# SCHEMATIC.net
KiCad netlist of a schematic drawn in EAGLE
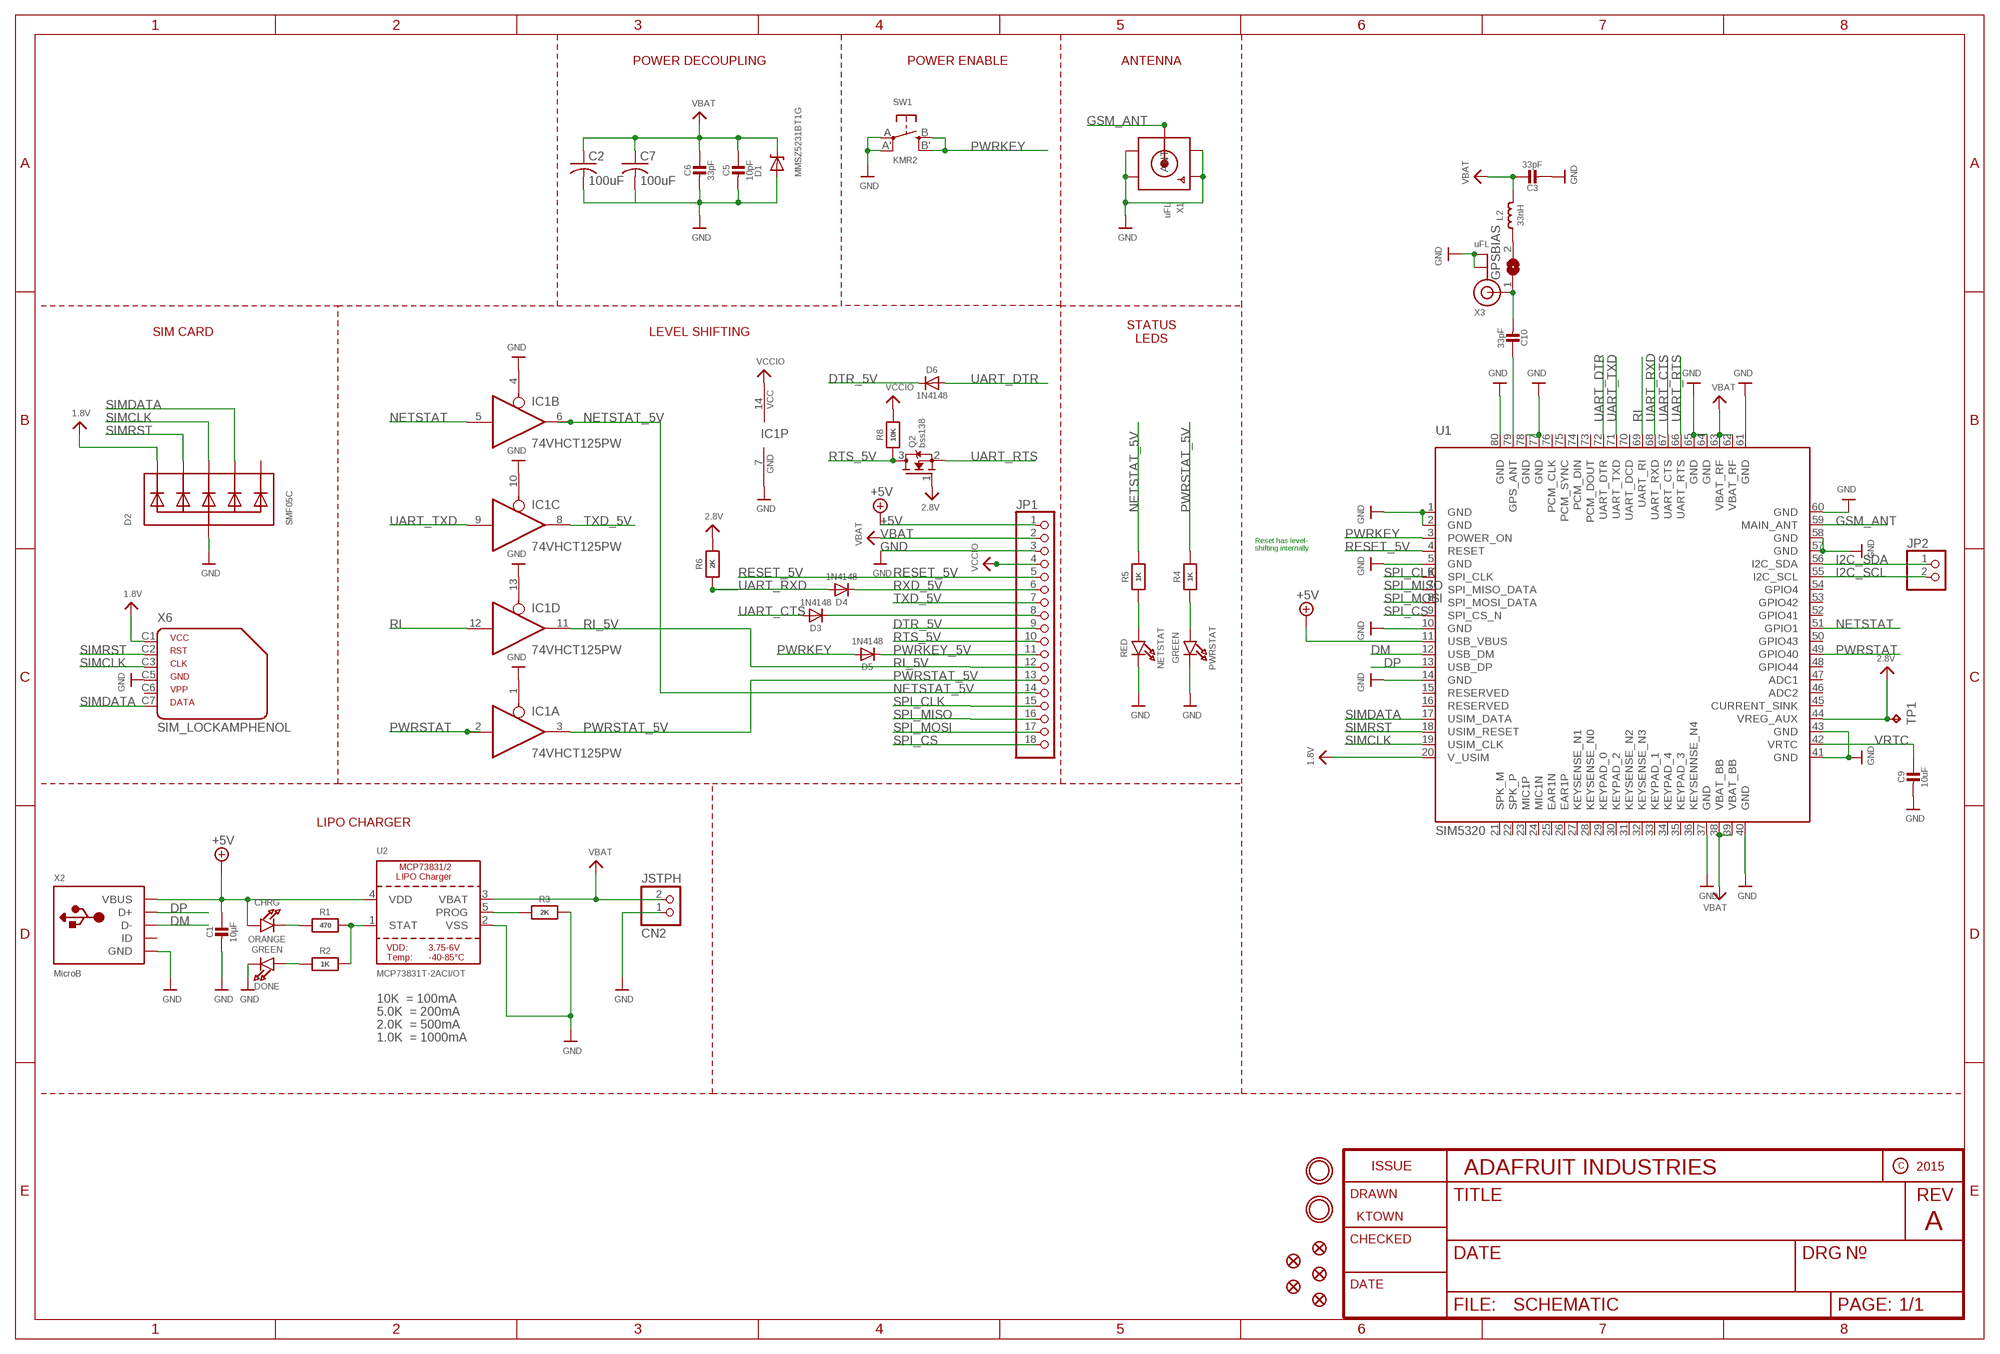
[diagram p0: schematic, sheet 1]

(export (version "E")
  (design (tool "Eeschema 10.0.6"))
  (components
    (comp (ref "C1")
      (value "10µF")
      (footprint "eagle-import:0805-NO")
      (libsource (lib "eagle-import") (part "CAP_CERAMIC0805-NOOUTLINE"))
    )
    (comp (ref "C2")
      (value "100uF")
      (footprint "eagle-import:C1210")
      (libsource (lib "eagle-import") (part "C-USC1210"))
    )
    (comp (ref "C3")
      (value "33pF")
      (footprint "eagle-import:0805-NO")
      (libsource (lib "eagle-import") (part "CAP_CERAMIC0805-NOOUTLINE"))
    )
    (comp (ref "C5")
      (value "10pF")
      (footprint "eagle-import:0805-NO")
      (libsource (lib "eagle-import") (part "CAP_CERAMIC0805-NOOUTLINE"))
    )
    (comp (ref "C6")
      (value "33pF")
      (footprint "eagle-import:0805-NO")
      (libsource (lib "eagle-import") (part "CAP_CERAMIC0805-NOOUTLINE"))
    )
    (comp (ref "C7")
      (value "100uF")
      (footprint "eagle-import:C1210")
      (libsource (lib "eagle-import") (part "C-USC1210"))
    )
    (comp (ref "C9")
      (value "10uF")
      (footprint "eagle-import:0805-NO")
      (libsource (lib "eagle-import") (part "CAP_CERAMIC0805-NOOUTLINE"))
    )
    (comp (ref "C10")
      (value "33pF")
      (footprint "eagle-import:0805-NO")
      (libsource (lib "eagle-import") (part "CAP_CERAMIC0805-NOOUTLINE"))
    )
    (comp (ref "CHRG")
      (value "ORANGE")
      (footprint "eagle-import:CHIPLED_0805_NOOUTLINE")
      (libsource (lib "eagle-import") (part "LED0805_NOOUTLINE"))
    )
    (comp (ref "CN2")
      (value "JSTPH")
      (footprint "eagle-import:JSTPH2")
      (libsource (lib "eagle-import") (part "JST_2PIN"))
    )
    (comp (ref "D1")
      (value "MMSZ5231BT1G")
      (footprint "eagle-import:SOD-123")
      (libsource (lib "eagle-import") (part "DIODE-ZENERSOD123"))
    )
    (comp (ref "D2")
      (value "SMF05C")
      (footprint "eagle-import:SOT363")
      (libsource (lib "eagle-import") (part "TVSARRAY_5LANE"))
    )
    (comp (ref "D3")
      (value "1N4148")
      (footprint "eagle-import:SOD-323")
      (libsource (lib "eagle-import") (part "DIODESOD-323"))
    )
    (comp (ref "D4")
      (value "1N4148")
      (footprint "eagle-import:SOD-323")
      (libsource (lib "eagle-import") (part "DIODESOD-323"))
    )
    (comp (ref "D5")
      (value "1N4148")
      (footprint "eagle-import:SOD-323")
      (libsource (lib "eagle-import") (part "DIODESOD-323"))
    )
    (comp (ref "D6")
      (value "1N4148")
      (footprint "eagle-import:SOD-323")
      (libsource (lib "eagle-import") (part "DIODESOD-323"))
    )
    (comp (ref "DONE")
      (value "GREEN")
      (footprint "eagle-import:CHIPLED_0805_NOOUTLINE")
      (libsource (lib "eagle-import") (part "LED0805_NOOUTLINE"))
    )
    (comp (ref "FID1")
      (value "FIDUCIAL\"\"")
      (footprint "eagle-import:FIDUCIAL_1MM")
      (libsource (lib "eagle-import") (part "FIDUCIAL{dblquote}{dblquote}"))
    )
    (comp (ref "FID2")
      (value "FIDUCIAL\"\"")
      (footprint "eagle-import:FIDUCIAL_1MM")
      (libsource (lib "eagle-import") (part "FIDUCIAL{dblquote}{dblquote}"))
    )
    (comp (ref "FID3")
      (value "FIDUCIAL\"\"")
      (footprint "eagle-import:FIDUCIAL_1MM")
      (libsource (lib "eagle-import") (part "FIDUCIAL{dblquote}{dblquote}"))
    )
    (comp (ref "FID4")
      (value "FIDUCIAL\"\"")
      (footprint "eagle-import:FIDUCIAL_1MM")
      (libsource (lib "eagle-import") (part "FIDUCIAL{dblquote}{dblquote}"))
    )
    (comp (ref "FID5")
      (value "FIDUCIAL\"\"")
      (footprint "eagle-import:FIDUCIAL_1MM")
      (libsource (lib "eagle-import") (part "FIDUCIAL{dblquote}{dblquote}"))
    )
    (comp (ref "GPSBIAS")
      (value "SOLDERJUMPER")
      (footprint "eagle-import:SOLDERJUMPER_ARROW_NOPASTE")
      (libsource (lib "eagle-import") (part "SOLDERJUMPER"))
    )
    (comp (ref "IC1")
      (value "74VHCT125PW")
      (footprint "eagle-import:TSSOP14")
      (libsource (lib "eagle-import") (part "74125PWABT"))
    )
    (comp (ref "JP1")
      (value "HEADER-1X18")
      (footprint "eagle-import:1X18_ROUND70")
      (libsource (lib "eagle-import") (part "HEADER-1X18"))
    )
    (comp (ref "JP2")
      (value "HEADER-1X2ROUND")
      (footprint "eagle-import:1X02_ROUND")
      (libsource (lib "eagle-import") (part "HEADER-1X2ROUND"))
    )
    (comp (ref "L2")
      (value "33nH")
      (footprint "eagle-import:_0805MP")
      (libsource (lib "eagle-import") (part "INDUCTOR_0805MP"))
    )
    (comp (ref "NETSTAT")
      (value "RED")
      (footprint "eagle-import:CHIPLED_0805_NOOUTLINE")
      (libsource (lib "eagle-import") (part "LED0805_NOOUTLINE"))
    )
    (comp (ref "PWRSTAT")
      (value "GREEN")
      (footprint "eagle-import:CHIPLED_0805_NOOUTLINE")
      (libsource (lib "eagle-import") (part "LED0805_NOOUTLINE"))
    )
    (comp (ref "Q2")
      (value "bss138")
      (footprint "eagle-import:SOT23-WIDE")
      (libsource (lib "eagle-import") (part "MOSFET-NWIDE"))
    )
    (comp (ref "R1")
      (value "470")
      (footprint "eagle-import:0805-NO")
      (libsource (lib "eagle-import") (part "RESISTOR0805_NOOUTLINE"))
    )
    (comp (ref "R2")
      (value "1K")
      (footprint "eagle-import:0805-NO")
      (libsource (lib "eagle-import") (part "RESISTOR0805_NOOUTLINE"))
    )
    (comp (ref "R3")
      (value "2K")
      (footprint "eagle-import:0805-NO")
      (libsource (lib "eagle-import") (part "RESISTOR0805_NOOUTLINE"))
    )
    (comp (ref "R4")
      (value "1K")
      (footprint "eagle-import:0805-NO")
      (libsource (lib "eagle-import") (part "RESISTOR0805_NOOUTLINE"))
    )
    (comp (ref "R5")
      (value "1K")
      (footprint "eagle-import:0805-NO")
      (libsource (lib "eagle-import") (part "RESISTOR0805_NOOUTLINE"))
    )
    (comp (ref "R6")
      (value "2K")
      (footprint "eagle-import:0805-NO")
      (libsource (lib "eagle-import") (part "RESISTOR0805_NOOUTLINE"))
    )
    (comp (ref "R8")
      (value "10K")
      (footprint "eagle-import:0805-NO")
      (libsource (lib "eagle-import") (part "RESISTOR0805_NOOUTLINE"))
    )
    (comp (ref "SW1")
      (value "KMR2")
      (footprint "eagle-import:BTN_KMR2_4.6X2.8")
      (libsource (lib "eagle-import") (part "SWITCH_TACT_SMT4.6X2.8"))
    )
    (comp (ref "TP1")
      (value "TPTP11R")
      (footprint "eagle-import:TP11R")
      (libsource (lib "eagle-import") (part "TPTP11R"))
    )
    (comp (ref "U$33")
      (value "MOUNTINGHOLE2.5")
      (footprint "eagle-import:MOUNTINGHOLE_2.5_PLATED")
      (libsource (lib "eagle-import") (part "MOUNTINGHOLE2.5"))
    )
    (comp (ref "U$34")
      (value "MOUNTINGHOLE2.5")
      (footprint "eagle-import:MOUNTINGHOLE_2.5_PLATED")
      (libsource (lib "eagle-import") (part "MOUNTINGHOLE2.5"))
    )
    (comp (ref "U1")
      (value "SIM5320")
      (footprint "eagle-import:SIM5320")
      (libsource (lib "eagle-import") (part "GSM_SIM5320_LITERAL"))
    )
    (comp (ref "U2")
      (value "MCP73831T-2ACI/OT")
      (footprint "eagle-import:SOT23-5")
      (libsource (lib "eagle-import") (part "MCP73831/2"))
    )
    (comp (ref "X1")
      (value "uFL")
      (footprint "eagle-import:SMA_EDGELAUNCH_UFL")
      (libsource (lib "eagle-import") (part "SMACONNECTOR_EDGE_UFL"))
    )
    (comp (ref "X2")
      (value "MicroB")
      (footprint "eagle-import:4UCONN_20329")
      (libsource (lib "eagle-import") (part "USBMICRO_20329"))
    )
    (comp (ref "X3")
      (value "uFL")
      (footprint "eagle-import:U.FL")
      (libsource (lib "eagle-import") (part "ANTENNA_U.FL"))
    )
    (comp (ref "X6")
      (value "SIM_LOCKAMPHENOL")
      (footprint "eagle-import:C707_10M006_512_2")
      (libsource (lib "eagle-import") (part "SIM_LOCKAMPHENOL"))
    )
  )
  (nets
    (net (code "1") (name "+5V") (class "Default")
      (node (ref "C1") (pin "1") (pinfunction "1_1") (pintype "passive"))
      (node (ref "CHRG") (pin "A") (pinfunction "A_A") (pintype "passive"))
      (node (ref "JP1") (pin "1") (pinfunction "1_1") (pintype "passive"))
      (node (ref "U1") (pin "11") (pinfunction "USB_VBUS_11") (pintype "bidirectional"))
      (node (ref "U2") (pin "4") (pinfunction "VDD_4") (pintype "power_in"))
      (node (ref "X2") (pin "VBUS") (pinfunction "VBUS_VBUS") (pintype "power_in"))
    )
    (net (code "2") (name "/DM") (class "Default")
      (node (ref "U1") (pin "12") (pinfunction "USB_DM_12") (pintype "bidirectional"))
      (node (ref "X2") (pin "D-") (pinfunction "D-_D-") (pintype "bidirectional"))
    )
    (net (code "3") (name "/DP") (class "Default")
      (node (ref "U1") (pin "13") (pinfunction "USB_DP_13") (pintype "bidirectional"))
      (node (ref "X2") (pin "D+") (pinfunction "D+_D+") (pintype "bidirectional"))
    )
    (net (code "4") (name "/DTR_5V") (class "Default")
      (node (ref "D6") (pin "C") (pinfunction "C_C") (pintype "passive"))
      (node (ref "JP1") (pin "9") (pinfunction "9_9") (pintype "passive"))
    )
    (net (code "5") (name "/GSM_ANT") (class "Default")
      (node (ref "U1") (pin "59") (pinfunction "MAIN_ANT_59") (pintype "bidirectional"))
      (node (ref "X1") (pin "P") (pinfunction "ANT_P") (pintype "bidirectional"))
    )
    (net (code "6") (name "/I2C_SCL") (class "Default")
      (node (ref "JP2") (pin "2") (pinfunction "2_2") (pintype "passive"))
      (node (ref "U1") (pin "55") (pinfunction "I2C_SCL_55") (pintype "bidirectional"))
    )
    (net (code "7") (name "/I2C_SDA") (class "Default")
      (node (ref "JP2") (pin "1") (pinfunction "1_1") (pintype "passive"))
      (node (ref "U1") (pin "56") (pinfunction "I2C_SDA_56") (pintype "bidirectional"))
    )
    (net (code "8") (name "/NETSTAT") (class "Default")
      (node (ref "IC1") (pin "5") (pinfunction "I_5") (pintype "input"))
      (node (ref "U1") (pin "51") (pinfunction "GPIO1_51") (pintype "bidirectional"))
    )
    (net (code "9") (name "/NETSTAT_5V") (class "Default")
      (node (ref "IC1") (pin "6") (pinfunction "O_6") (pintype "tri_state"))
      (node (ref "JP1") (pin "14") (pinfunction "14_14") (pintype "passive"))
      (node (ref "R5") (pin "2") (pinfunction "2_2") (pintype "passive"))
    )
    (net (code "10") (name "/PWRKEY") (class "Default")
      (node (ref "D5") (pin "A") (pinfunction "A_A") (pintype "passive"))
      (node (ref "SW1") (pin "B") (pinfunction "S_B") (pintype "passive"))
      (node (ref "SW1") (pin "B'") (pinfunction "S1_B'") (pintype "passive"))
      (node (ref "U1") (pin "3") (pinfunction "POWER_ON_3") (pintype "bidirectional"))
    )
    (net (code "11") (name "/PWRKEY_5V") (class "Default")
      (node (ref "D5") (pin "C") (pinfunction "C_C") (pintype "passive"))
      (node (ref "JP1") (pin "11") (pinfunction "11_11") (pintype "passive"))
    )
    (net (code "12") (name "/PWRSTAT") (class "Default")
      (node (ref "IC1") (pin "2") (pinfunction "I_2") (pintype "input"))
      (node (ref "U1") (pin "49") (pinfunction "GPIO40_49") (pintype "bidirectional"))
    )
    (net (code "13") (name "/PWRSTAT_5V") (class "Default")
      (node (ref "IC1") (pin "3") (pinfunction "O_3") (pintype "tri_state"))
      (node (ref "JP1") (pin "13") (pinfunction "13_13") (pintype "passive"))
      (node (ref "R4") (pin "2") (pinfunction "2_2") (pintype "passive"))
    )
    (net (code "14") (name "/RESET_5V") (class "Default")
      (node (ref "JP1") (pin "5") (pinfunction "5_5") (pintype "passive"))
      (node (ref "U1") (pin "4") (pinfunction "RESET_4") (pintype "bidirectional"))
    )
    (net (code "15") (name "/RI") (class "Default")
      (node (ref "IC1") (pin "12") (pinfunction "I_12") (pintype "input"))
      (node (ref "U1") (pin "69") (pinfunction "UART_RI_69") (pintype "bidirectional"))
    )
    (net (code "16") (name "/RI_5V") (class "Default")
      (node (ref "IC1") (pin "11") (pinfunction "O_11") (pintype "tri_state"))
      (node (ref "JP1") (pin "12") (pinfunction "12_12") (pintype "passive"))
    )
    (net (code "17") (name "/RTS_5V") (class "Default")
      (node (ref "JP1") (pin "10") (pinfunction "10_10") (pintype "passive"))
      (node (ref "Q2") (pin "3") (pinfunction "D_3") (pintype "bidirectional"))
      (node (ref "R8") (pin "1") (pinfunction "1_1") (pintype "passive"))
    )
    (net (code "18") (name "/RXD_5V") (class "Default")
      (node (ref "D4") (pin "C") (pinfunction "C_C") (pintype "passive"))
      (node (ref "JP1") (pin "6") (pinfunction "6_6") (pintype "passive"))
    )
    (net (code "19") (name "/SIMCLK") (class "Default")
      (node (ref "D2") (pin "4") (pinfunction "C3_4") (pintype "passive"))
      (node (ref "U1") (pin "19") (pinfunction "USIM_CLK_19") (pintype "bidirectional"))
      (node (ref "X6") (pin "C3") (pinfunction "3_C3") (pintype "passive"))
    )
    (net (code "20") (name "/SIMDATA") (class "Default")
      (node (ref "D2") (pin "5") (pinfunction "C4_5") (pintype "passive"))
      (node (ref "U1") (pin "17") (pinfunction "USIM_DATA_17") (pintype "bidirectional"))
      (node (ref "X6") (pin "C7") (pinfunction "6_C7") (pintype "passive"))
    )
    (net (code "21") (name "/SIMRST") (class "Default")
      (node (ref "D2") (pin "3") (pinfunction "C2_3") (pintype "passive"))
      (node (ref "U1") (pin "18") (pinfunction "USIM_RESET_18") (pintype "bidirectional"))
      (node (ref "X6") (pin "C2") (pinfunction "2_C2") (pintype "passive"))
    )
    (net (code "22") (name "/SPI_CLK") (class "Default")
      (node (ref "JP1") (pin "15") (pinfunction "15_15") (pintype "passive"))
      (node (ref "U1") (pin "6") (pinfunction "SPI_CLK_6") (pintype "bidirectional"))
    )
    (net (code "23") (name "/SPI_CS") (class "Default")
      (node (ref "JP1") (pin "18") (pinfunction "18_18") (pintype "passive"))
      (node (ref "U1") (pin "9") (pinfunction "SPI_CS_N_9") (pintype "bidirectional"))
    )
    (net (code "24") (name "/SPI_MISO") (class "Default")
      (node (ref "JP1") (pin "16") (pinfunction "16_16") (pintype "passive"))
      (node (ref "U1") (pin "7") (pinfunction "SPI_MISO_DATA_7") (pintype "bidirectional"))
    )
    (net (code "25") (name "/SPI_MOSI") (class "Default")
      (node (ref "JP1") (pin "17") (pinfunction "17_17") (pintype "passive"))
      (node (ref "U1") (pin "8") (pinfunction "SPI_MOSI_DATA_8") (pintype "bidirectional"))
    )
    (net (code "26") (name "/TXD_5V") (class "Default")
      (node (ref "IC1") (pin "8") (pinfunction "O_8") (pintype "tri_state"))
      (node (ref "JP1") (pin "7") (pinfunction "7_7") (pintype "passive"))
    )
    (net (code "27") (name "/UART_CTS") (class "Default")
      (node (ref "D3") (pin "A") (pinfunction "A_A") (pintype "passive"))
      (node (ref "U1") (pin "67") (pinfunction "UART_CTS_67") (pintype "bidirectional"))
    )
    (net (code "28") (name "/UART_DTR") (class "Default")
      (node (ref "D6") (pin "A") (pinfunction "A_A") (pintype "passive"))
      (node (ref "U1") (pin "72") (pinfunction "UART_DTR_72") (pintype "bidirectional"))
    )
    (net (code "29") (name "/UART_RTS") (class "Default")
      (node (ref "Q2") (pin "2") (pinfunction "S_2") (pintype "bidirectional"))
      (node (ref "U1") (pin "66") (pinfunction "UART_RTS_66") (pintype "bidirectional"))
    )
    (net (code "30") (name "/UART_RXD") (class "Default")
      (node (ref "D4") (pin "A") (pinfunction "A_A") (pintype "passive"))
      (node (ref "R6") (pin "1") (pinfunction "1_1") (pintype "passive"))
      (node (ref "U1") (pin "68") (pinfunction "UART_RXD_68") (pintype "bidirectional"))
    )
    (net (code "31") (name "/UART_TXD") (class "Default")
      (node (ref "IC1") (pin "9") (pinfunction "I_9") (pintype "input"))
      (node (ref "U1") (pin "71") (pinfunction "UART_TXD_71") (pintype "bidirectional"))
    )
    (net (code "32") (name "/VRTC") (class "Default")
      (node (ref "C9") (pin "1") (pinfunction "1_1") (pintype "passive"))
      (node (ref "U1") (pin "42") (pinfunction "VRTC_42") (pintype "bidirectional"))
    )
    (net (code "33") (name "1.8V") (class "Default")
      (node (ref "D2") (pin "1") (pinfunction "C1_1") (pintype "passive"))
      (node (ref "U1") (pin "20") (pinfunction "V_USIM_20") (pintype "bidirectional"))
      (node (ref "X6") (pin "C1") (pinfunction "1_C1") (pintype "passive"))
    )
    (net (code "34") (name "2.8V") (class "Default")
      (node (ref "Q2") (pin "1") (pinfunction "G_1") (pintype "bidirectional"))
      (node (ref "R6") (pin "2") (pinfunction "2_2") (pintype "passive"))
      (node (ref "TP1") (pin "TP") (pinfunction "TP_TP") (pintype "input"))
      (node (ref "U1") (pin "44") (pinfunction "VREG_AUX_44") (pintype "bidirectional"))
    )
    (net (code "35") (name "GND") (class "Default")
      (node (ref "C1") (pin "2") (pinfunction "2_2") (pintype "passive"))
      (node (ref "C2") (pin "2") (pinfunction "2_2") (pintype "passive"))
      (node (ref "C3") (pin "2") (pinfunction "2_2") (pintype "passive"))
      (node (ref "C5") (pin "2") (pinfunction "2_2") (pintype "passive"))
      (node (ref "C6") (pin "2") (pinfunction "2_2") (pintype "passive"))
      (node (ref "C7") (pin "2") (pinfunction "2_2") (pintype "passive"))
      (node (ref "C9") (pin "2") (pinfunction "2_2") (pintype "passive"))
      (node (ref "CN2") (pin "1") (pinfunction "1_1") (pintype "passive"))
      (node (ref "D1") (pin "A") (pinfunction "A_A") (pintype "passive"))
      (node (ref "D2") (pin "2") (pinfunction "A_2") (pintype "passive"))
      (node (ref "DONE") (pin "C") (pinfunction "C_C") (pintype "passive"))
      (node (ref "IC1") (pin "1") (pinfunction "OE_1") (pintype "input"))
      (node (ref "IC1") (pin "10") (pinfunction "OE_10") (pintype "input"))
      (node (ref "IC1") (pin "13") (pinfunction "OE_13") (pintype "input"))
      (node (ref "IC1") (pin "4") (pinfunction "OE_4") (pintype "input"))
      (node (ref "IC1") (pin "7") (pinfunction "GND_7") (pintype "power_in"))
      (node (ref "JP1") (pin "3") (pinfunction "3_3") (pintype "passive"))
      (node (ref "NETSTAT") (pin "C") (pinfunction "C_C") (pintype "passive"))
      (node (ref "PWRSTAT") (pin "C") (pinfunction "C_C") (pintype "passive"))
      (node (ref "R3") (pin "2") (pinfunction "2_2") (pintype "passive"))
      (node (ref "SW1") (pin "A") (pinfunction "P_A") (pintype "passive"))
      (node (ref "SW1") (pin "A'") (pinfunction "P1_A'") (pintype "passive"))
      (node (ref "U1") (pin "1") (pinfunction "GND_1") (pintype "bidirectional"))
      (node (ref "U1") (pin "10") (pinfunction "GND_10") (pintype "bidirectional"))
      (node (ref "U1") (pin "14") (pinfunction "GND_14") (pintype "bidirectional"))
      (node (ref "U1") (pin "2") (pinfunction "GND_2") (pintype "bidirectional"))
      (node (ref "U1") (pin "37") (pinfunction "GND_37") (pintype "bidirectional"))
      (node (ref "U1") (pin "40") (pinfunction "GND_40") (pintype "bidirectional"))
      (node (ref "U1") (pin "41") (pinfunction "GND_41") (pintype "bidirectional"))
      (node (ref "U1") (pin "43") (pinfunction "GND_43") (pintype "bidirectional"))
      (node (ref "U1") (pin "5") (pinfunction "GND_5") (pintype "bidirectional"))
      (node (ref "U1") (pin "57") (pinfunction "GND_57") (pintype "bidirectional"))
      (node (ref "U1") (pin "58") (pinfunction "GND_58") (pintype "bidirectional"))
      (node (ref "U1") (pin "60") (pinfunction "GND_60") (pintype "bidirectional"))
      (node (ref "U1") (pin "61") (pinfunction "GND_61") (pintype "bidirectional"))
      (node (ref "U1") (pin "64") (pinfunction "GND_64") (pintype "bidirectional"))
      (node (ref "U1") (pin "65") (pinfunction "GND_65") (pintype "bidirectional"))
      (node (ref "U1") (pin "77") (pinfunction "GND_77") (pintype "bidirectional"))
      (node (ref "U1") (pin "78") (pinfunction "GND_78") (pintype "bidirectional"))
      (node (ref "U1") (pin "80") (pinfunction "GND_80") (pintype "bidirectional"))
      (node (ref "U2") (pin "2") (pinfunction "VSS_2") (pintype "power_in"))
      (node (ref "X1") (pin "GND@1") (pinfunction "GND1_GND@1") (pintype "power_in"))
      (node (ref "X1") (pin "GND@2") (pinfunction "GND2_GND@2") (pintype "power_in"))
      (node (ref "X1") (pin "GND@3") (pinfunction "GND3_GND@3") (pintype "power_in"))
      (node (ref "X1") (pin "GND@4") (pinfunction "GND4_GND@4") (pintype "power_in"))
      (node (ref "X2") (pin "BASE@1") (pinfunction "GND_BASE@1") (pintype "power_in"))
      (node (ref "X2") (pin "BASE@2") (pinfunction "GND_BASE@2") (pintype "power_in"))
      (node (ref "X2") (pin "GND") (pinfunction "GND_GND") (pintype "power_in"))
      (node (ref "X2") (pin "SPRT@1") (pinfunction "GND_SPRT@1") (pintype "power_in"))
      (node (ref "X2") (pin "SPRT@2") (pinfunction "GND_SPRT@2") (pintype "power_in"))
      (node (ref "X2") (pin "SPRT@3") (pinfunction "GND_SPRT@3") (pintype "power_in"))
      (node (ref "X2") (pin "SPRT@4") (pinfunction "GND_SPRT@4") (pintype "power_in"))
      (node (ref "X3") (pin "1") (pinfunction "GND_1") (pintype "passive"))
      (node (ref "X3") (pin "2") (pinfunction "GND_2") (pintype "passive"))
      (node (ref "X6") (pin "C5") (pinfunction "4_C5") (pintype "passive"))
    )
    (net (code "36") (name "Net-(CHRG-PadC)") (class "Default")
      (node (ref "CHRG") (pin "C") (pinfunction "C_C") (pintype "passive"))
      (node (ref "R1") (pin "1") (pinfunction "1_1") (pintype "passive"))
    )
    (net (code "37") (name "Net-(D3-PadC)") (class "Default")
      (node (ref "D3") (pin "C") (pinfunction "C_C") (pintype "passive"))
      (node (ref "JP1") (pin "8") (pinfunction "8_8") (pintype "passive"))
    )
    (net (code "38") (name "Net-(DONE-PadA)") (class "Default")
      (node (ref "DONE") (pin "A") (pinfunction "A_A") (pintype "passive"))
      (node (ref "R2") (pin "1") (pinfunction "1_1") (pintype "passive"))
    )
    (net (code "39") (name "Net-(GPSBIAS-Pad2)") (class "Default")
      (node (ref "GPSBIAS") (pin "2") (pinfunction "2_2") (pintype "passive"))
      (node (ref "L2") (pin "1") (pinfunction "1_1") (pintype "passive"))
    )
    (net (code "40") (name "Net-(NETSTAT-PadA)") (class "Default")
      (node (ref "NETSTAT") (pin "A") (pinfunction "A_A") (pintype "passive"))
      (node (ref "R5") (pin "1") (pinfunction "1_1") (pintype "passive"))
    )
    (net (code "41") (name "Net-(PWRSTAT-PadA)") (class "Default")
      (node (ref "PWRSTAT") (pin "A") (pinfunction "A_A") (pintype "passive"))
      (node (ref "R4") (pin "1") (pinfunction "1_1") (pintype "passive"))
    )
    (net (code "42") (name "Net-(U1-GPS_ANT)") (class "Default")
      (node (ref "C10") (pin "1") (pinfunction "1_1") (pintype "passive"))
      (node (ref "U1") (pin "79") (pinfunction "GPS_ANT_79") (pintype "bidirectional"))
    )
    (net (code "43") (name "Net-(U2-PROG)") (class "Default")
      (node (ref "R3") (pin "1") (pinfunction "1_1") (pintype "passive"))
      (node (ref "U2") (pin "5") (pinfunction "PROG_5") (pintype "input"))
    )
    (net (code "44") (name "Net-(U2-STAT)") (class "Default")
      (node (ref "R1") (pin "2") (pinfunction "2_2") (pintype "passive"))
      (node (ref "R2") (pin "2") (pinfunction "2_2") (pintype "passive"))
      (node (ref "U2") (pin "1") (pinfunction "STAT_1") (pintype "output"))
    )
    (net (code "45") (name "Net-(X3-SIGNAL)") (class "Default")
      (node (ref "C10") (pin "2") (pinfunction "2_2") (pintype "passive"))
      (node (ref "GPSBIAS") (pin "1") (pinfunction "1_1") (pintype "passive"))
      (node (ref "X3") (pin "3") (pinfunction "SIGNAL_3") (pintype "passive"))
    )
    (net (code "46") (name "VBAT") (class "Default")
      (node (ref "C2") (pin "1") (pinfunction "1_1") (pintype "passive"))
      (node (ref "C3") (pin "1") (pinfunction "1_1") (pintype "passive"))
      (node (ref "C5") (pin "1") (pinfunction "1_1") (pintype "passive"))
      (node (ref "C6") (pin "1") (pinfunction "1_1") (pintype "passive"))
      (node (ref "C7") (pin "1") (pinfunction "1_1") (pintype "passive"))
      (node (ref "CN2") (pin "2") (pinfunction "2_2") (pintype "passive"))
      (node (ref "D1") (pin "C") (pinfunction "C_C") (pintype "passive"))
      (node (ref "JP1") (pin "2") (pinfunction "2_2") (pintype "passive"))
      (node (ref "L2") (pin "2") (pinfunction "2_2") (pintype "passive"))
      (node (ref "U1") (pin "38") (pinfunction "VBAT_BB_38") (pintype "bidirectional"))
      (node (ref "U1") (pin "39") (pinfunction "VBAT_BB_39") (pintype "bidirectional"))
      (node (ref "U1") (pin "62") (pinfunction "VBAT_RF_62") (pintype "bidirectional"))
      (node (ref "U1") (pin "63") (pinfunction "VBAT_RF_63") (pintype "bidirectional"))
      (node (ref "U2") (pin "3") (pinfunction "VBAT_3") (pintype "power_in"))
    )
    (net (code "47") (name "VCCIO") (class "Default")
      (node (ref "IC1") (pin "14") (pinfunction "VCC_14") (pintype "power_in"))
      (node (ref "JP1") (pin "4") (pinfunction "4_4") (pintype "passive"))
      (node (ref "R8") (pin "2") (pinfunction "2_2") (pintype "passive"))
    )
    (net (code "48") (name "unconnected-(D2-C5-Pad6)") (class "Default")
      (node (ref "D2") (pin "6") (pinfunction "C5_6") (pintype "passive"))
    )
    (net (code "49") (name "unconnected-(U1-ADC1-Pad47)") (class "Default")
      (node (ref "U1") (pin "47") (pinfunction "ADC1_47") (pintype "bidirectional"))
    )
    (net (code "50") (name "unconnected-(U1-ADC2-Pad46)") (class "Default")
      (node (ref "U1") (pin "46") (pinfunction "ADC2_46") (pintype "bidirectional"))
    )
    (net (code "51") (name "unconnected-(U1-CURRENT_SINK-Pad45)") (class "Default")
      (node (ref "U1") (pin "45") (pinfunction "CURRENT_SINK_45") (pintype "bidirectional"))
    )
    (net (code "52") (name "unconnected-(U1-EAR1N-Pad25)") (class "Default")
      (node (ref "U1") (pin "25") (pinfunction "EAR1N_25") (pintype "bidirectional"))
    )
    (net (code "53") (name "unconnected-(U1-EAR1P-Pad26)") (class "Default")
      (node (ref "U1") (pin "26") (pinfunction "EAR1P_26") (pintype "bidirectional"))
    )
    (net (code "54") (name "unconnected-(U1-GPIO4-Pad54)") (class "Default")
      (node (ref "U1") (pin "54") (pinfunction "GPIO4_54") (pintype "bidirectional"))
    )
    (net (code "55") (name "unconnected-(U1-GPIO41-Pad52)") (class "Default")
      (node (ref "U1") (pin "52") (pinfunction "GPIO41_52") (pintype "bidirectional"))
    )
    (net (code "56") (name "unconnected-(U1-GPIO42-Pad53)") (class "Default")
      (node (ref "U1") (pin "53") (pinfunction "GPIO42_53") (pintype "bidirectional"))
    )
    (net (code "57") (name "unconnected-(U1-GPIO43-Pad50)") (class "Default")
      (node (ref "U1") (pin "50") (pinfunction "GPIO43_50") (pintype "bidirectional"))
    )
    (net (code "58") (name "unconnected-(U1-GPIO44-Pad48)") (class "Default")
      (node (ref "U1") (pin "48") (pinfunction "GPIO44_48") (pintype "bidirectional"))
    )
    (net (code "59") (name "unconnected-(U1-KEYPAD_0-Pad29)") (class "Default")
      (node (ref "U1") (pin "29") (pinfunction "KEYPAD_0_29") (pintype "bidirectional"))
    )
    (net (code "60") (name "unconnected-(U1-KEYPAD_1-Pad33)") (class "Default")
      (node (ref "U1") (pin "33") (pinfunction "KEYPAD_1_33") (pintype "bidirectional"))
    )
    (net (code "61") (name "unconnected-(U1-KEYPAD_2-Pad30)") (class "Default")
      (node (ref "U1") (pin "30") (pinfunction "KEYPAD_2_30") (pintype "bidirectional"))
    )
    (net (code "62") (name "unconnected-(U1-KEYPAD_3-Pad35)") (class "Default")
      (node (ref "U1") (pin "35") (pinfunction "KEYPAD_3_35") (pintype "bidirectional"))
    )
    (net (code "63") (name "unconnected-(U1-KEYPAD_4-Pad34)") (class "Default")
      (node (ref "U1") (pin "34") (pinfunction "KEYPAD_4_34") (pintype "bidirectional"))
    )
    (net (code "64") (name "unconnected-(U1-KEYSENNSE_N4-Pad36)") (class "Default")
      (node (ref "U1") (pin "36") (pinfunction "KEYSENNSE_N4_36") (pintype "bidirectional"))
    )
    (net (code "65") (name "unconnected-(U1-KEYSENSE_N0-Pad28)") (class "Default")
      (node (ref "U1") (pin "28") (pinfunction "KEYSENSE_N0_28") (pintype "bidirectional"))
    )
    (net (code "66") (name "unconnected-(U1-KEYSENSE_N1-Pad27)") (class "Default")
      (node (ref "U1") (pin "27") (pinfunction "KEYSENSE_N1_27") (pintype "bidirectional"))
    )
    (net (code "67") (name "unconnected-(U1-KEYSENSE_N2-Pad31)") (class "Default")
      (node (ref "U1") (pin "31") (pinfunction "KEYSENSE_N2_31") (pintype "bidirectional"))
    )
    (net (code "68") (name "unconnected-(U1-KEYSENSE_N3-Pad32)") (class "Default")
      (node (ref "U1") (pin "32") (pinfunction "KEYSENSE_N3_32") (pintype "bidirectional"))
    )
    (net (code "69") (name "unconnected-(U1-MIC1N-Pad24)") (class "Default")
      (node (ref "U1") (pin "24") (pinfunction "MIC1N_24") (pintype "bidirectional"))
    )
    (net (code "70") (name "unconnected-(U1-MIC1P-Pad23)") (class "Default")
      (node (ref "U1") (pin "23") (pinfunction "MIC1P_23") (pintype "bidirectional"))
    )
    (net (code "71") (name "unconnected-(U1-PCM_CLK-Pad76)") (class "Default")
      (node (ref "U1") (pin "76") (pinfunction "PCM_CLK_76") (pintype "bidirectional"))
    )
    (net (code "72") (name "unconnected-(U1-PCM_DIN-Pad74)") (class "Default")
      (node (ref "U1") (pin "74") (pinfunction "PCM_DIN_74") (pintype "bidirectional"))
    )
    (net (code "73") (name "unconnected-(U1-PCM_DOUT-Pad73)") (class "Default")
      (node (ref "U1") (pin "73") (pinfunction "PCM_DOUT_73") (pintype "bidirectional"))
    )
    (net (code "74") (name "unconnected-(U1-PCM_SYNC-Pad75)") (class "Default")
      (node (ref "U1") (pin "75") (pinfunction "PCM_SYNC_75") (pintype "bidirectional"))
    )
    (net (code "75") (name "unconnected-(U1-RESERVED-Pad15)") (class "Default")
      (node (ref "U1") (pin "15") (pinfunction "RESERVED_15") (pintype "bidirectional"))
    )
    (net (code "76") (name "unconnected-(U1-RESERVED-Pad16)") (class "Default")
      (node (ref "U1") (pin "16") (pinfunction "RESERVED_16") (pintype "bidirectional"))
    )
    (net (code "77") (name "unconnected-(U1-SPK_M-Pad21)") (class "Default")
      (node (ref "U1") (pin "21") (pinfunction "SPK_M_21") (pintype "bidirectional"))
    )
    (net (code "78") (name "unconnected-(U1-SPK_P-Pad22)") (class "Default")
      (node (ref "U1") (pin "22") (pinfunction "SPK_P_22") (pintype "bidirectional"))
    )
    (net (code "79") (name "unconnected-(U1-UART_DCD-Pad70)") (class "Default")
      (node (ref "U1") (pin "70") (pinfunction "UART_DCD_70") (pintype "bidirectional"))
    )
    (net (code "80") (name "unconnected-(X2-PadID)") (class "Default")
      (node (ref "X2") (pin "ID") (pinfunction "ID_ID") (pintype "bidirectional"))
    )
    (net (code "81") (name "unconnected-(X6-5-PadC6)") (class "Default")
      (node (ref "X6") (pin "C6") (pinfunction "5_C6") (pintype "passive"))
    )
  )
)
